# SPIBreakout.net
KiCad netlist of a schematic drawn in EAGLE
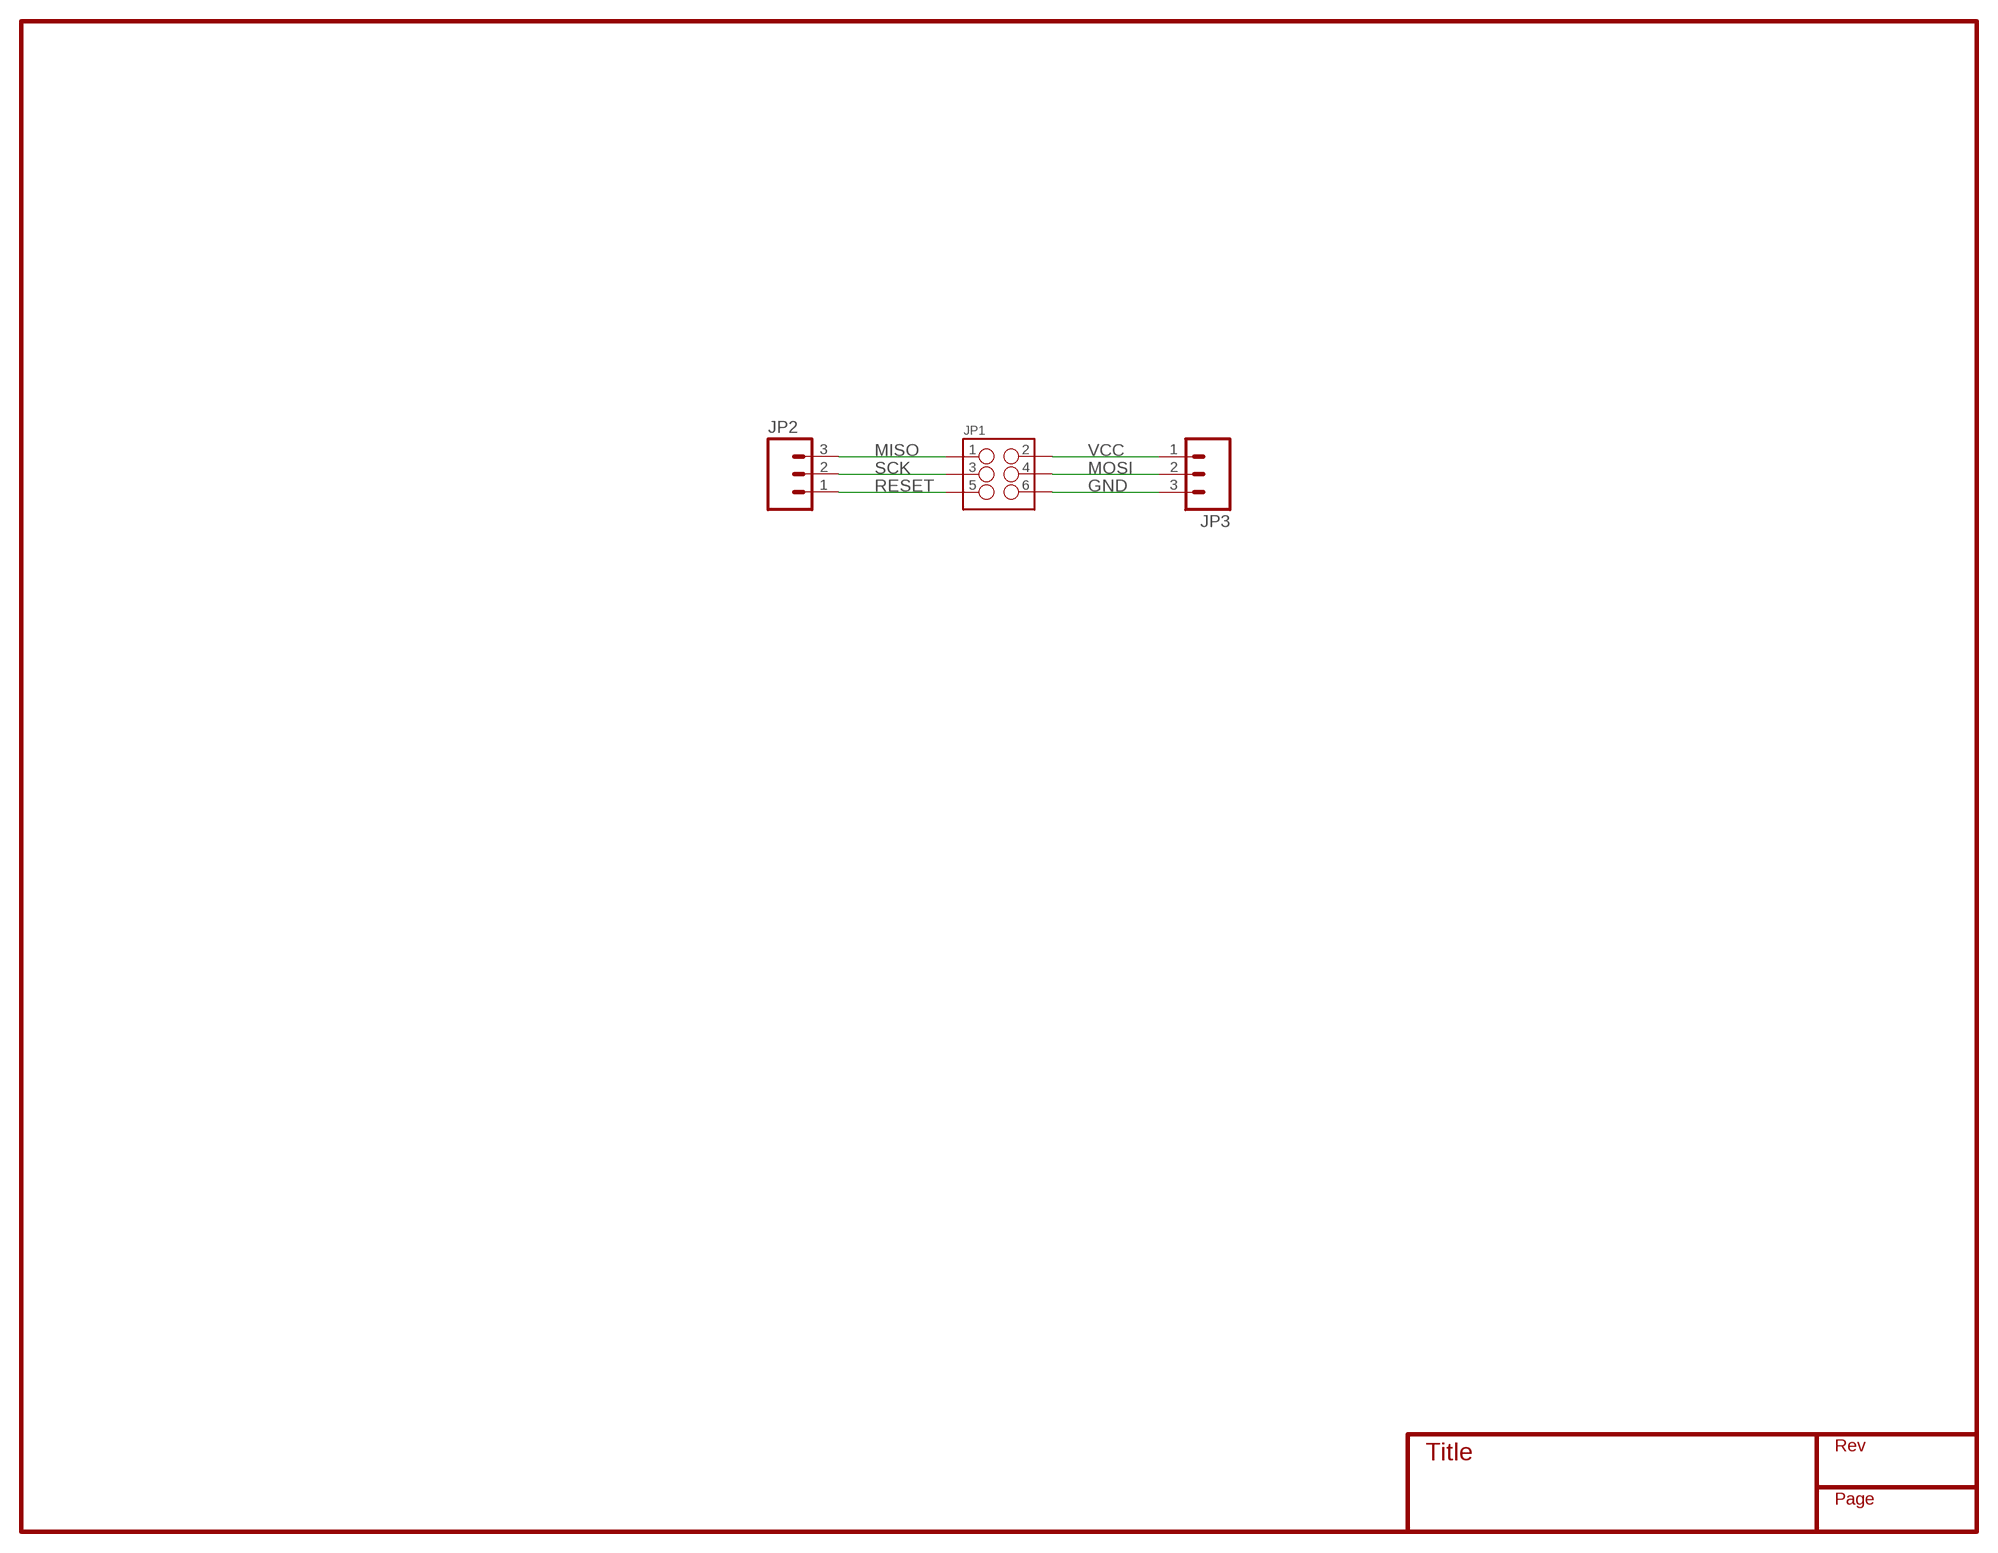
[diagram p0: schematic, sheet 1]

(export (version "E")
  (design (tool "Eeschema 10.0.6"))
  (components
    (comp (ref "JP1")
      (value "M03X2FEMALE")
      (footprint "eagle-import:2X3")
      (libsource (lib "eagle-import") (part "M03X2FEMALE"))
    )
    (comp (ref "JP2")
      (value "M03PTH")
      (footprint "eagle-import:1X03")
      (libsource (lib "eagle-import") (part "M03PTH"))
    )
    (comp (ref "JP3")
      (value "M03PTH")
      (footprint "eagle-import:1X03")
      (libsource (lib "eagle-import") (part "M03PTH"))
    )
  )
  (nets
    (net (code "1") (name "/GND") (class "Default")
      (node (ref "JP1") (pin "6") (pinfunction "6_6") (pintype "bidirectional"))
      (node (ref "JP3") (pin "3") (pinfunction "3_3") (pintype "passive"))
    )
    (net (code "2") (name "/MISO") (class "Default")
      (node (ref "JP1") (pin "1") (pinfunction "1_1") (pintype "bidirectional"))
      (node (ref "JP2") (pin "3") (pinfunction "3_3") (pintype "passive"))
    )
    (net (code "3") (name "/MOSI") (class "Default")
      (node (ref "JP1") (pin "4") (pinfunction "4_4") (pintype "bidirectional"))
      (node (ref "JP3") (pin "2") (pinfunction "2_2") (pintype "passive"))
    )
    (net (code "4") (name "/RESET") (class "Default")
      (node (ref "JP1") (pin "5") (pinfunction "5_5") (pintype "bidirectional"))
      (node (ref "JP2") (pin "1") (pinfunction "1_1") (pintype "passive"))
    )
    (net (code "5") (name "/SCK") (class "Default")
      (node (ref "JP1") (pin "3") (pinfunction "3_3") (pintype "bidirectional"))
      (node (ref "JP2") (pin "2") (pinfunction "2_2") (pintype "passive"))
    )
    (net (code "6") (name "/VCC") (class "Default")
      (node (ref "JP1") (pin "2") (pinfunction "2_2") (pintype "bidirectional"))
      (node (ref "JP3") (pin "1") (pinfunction "1_1") (pintype "passive"))
    )
  )
)
